# Rotary_Encoder.net
KiCad netlist of a schematic drawn in Altium Designer
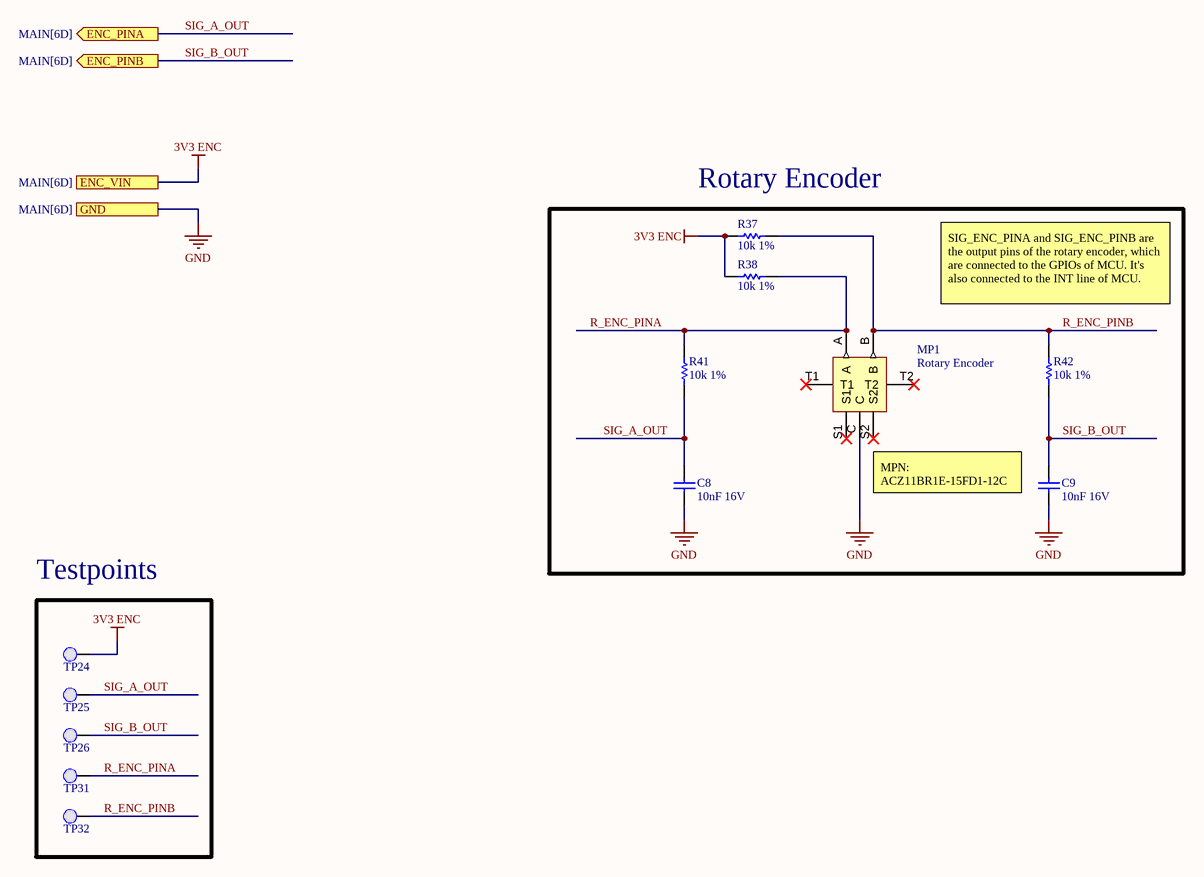
[diagram p0: Rotary Encoder.SchDoc]

(export (version "E")
  (design (tool "Eeschema 10.0.6"))
  (components
    (comp (ref "C8")
      (value "10nF 16V")
      (footprint "CAPC1608X90")
      (description "Rotary Enc-Cap Cer 0603 10NF 16V X7R 10%")
      (fields
        (field (name "MANUFACTURER") "KEMET")
        (field (name "MANUFACTURER PART NUMBER") "C0603C103K4REC7867")
      )
      (libsource (lib "Schlib1") (part "C0603C103K4REC7867"))
    )
    (comp (ref "C9")
      (value "10nF 16V")
      (footprint "CAPC1608X90")
      (description "Rotary Enc-Cap Cer 0603 10NF 16V X7R 10%")
      (fields
        (field (name "MANUFACTURER") "KEMET")
        (field (name "MANUFACTURER PART NUMBER") "C0603C103K4REC7867")
      )
      (libsource (lib "Schlib1") (part "C0603C103K4REC7867"))
    )
    (comp (ref "MP1")
      (value "Rotary Encoder")
      (footprint "Rotary Encoder")
      (description "MPN: ACZ11BR1E-15FD1-12C")
      (libsource (lib "Schlib1") (part "Rotary Encoder"))
    )
    (comp (ref "R37")
      (value "10k 1%")
      (footprint "RESC1608X55X25ML10T15")
      (description "AF0603FR-0710KL")
      (fields (field (name "MANUFACTURER") "Yageo"))
      (libsource (lib "Altium Content Vault") (part "RES"))
    )
    (comp (ref "R38")
      (value "10k 1%")
      (footprint "RESC1608X55X25ML10T15")
      (description "AF0603FR-0710KL")
      (fields (field (name "MANUFACTURER") "Yageo"))
      (libsource (lib "Altium Content Vault") (part "RES"))
    )
    (comp (ref "R41")
      (value "10k 1%")
      (footprint "RESC1608X55X25ML10T15")
      (description "AF0603FR-0710KL")
      (fields (field (name "MANUFACTURER") "Yageo"))
      (libsource (lib "Altium Content Vault") (part "RES"))
    )
    (comp (ref "R42")
      (value "10k 1%")
      (footprint "RESC1608X55X25ML10T15")
      (description "AF0603FR-0710KL")
      (fields (field (name "MANUFACTURER") "Yageo"))
      (libsource (lib "Altium Content Vault") (part "RES"))
    )
    (comp (ref "TP24")
      (value "0.1\" Pad")
      (footprint "PCBComponent")
      (libsource (lib "Components - 12.02.20 - 18.05") (part "0.1{dblquote} Pad-A.4"))
    )
    (comp (ref "TP25")
      (value "0.1\" Pad")
      (footprint "PCBComponent")
      (libsource (lib "Components - 12.02.20 - 18.05") (part "0.1{dblquote} Pad-A.4"))
    )
    (comp (ref "TP26")
      (value "0.1\" Pad")
      (footprint "PCBComponent")
      (libsource (lib "Components - 12.02.20 - 18.05") (part "0.1{dblquote} Pad-A.4"))
    )
    (comp (ref "TP31")
      (value "0.1\" Pad")
      (footprint "PCBComponent")
      (libsource (lib "Components - 12.02.20 - 18.05") (part "0.1{dblquote} Pad-A.4"))
    )
    (comp (ref "TP32")
      (value "0.1\" Pad")
      (footprint "PCBComponent")
      (libsource (lib "Components - 12.02.20 - 18.05") (part "0.1{dblquote} Pad-A.4"))
    )
  )
  (nets
    (net (code "1") (name "/R_ENC_PINA") (class "Default")
      (node (ref "MP1") (pin "A") (pinfunction "A_A") (pintype "output"))
      (node (ref "R38") (pin "1") (pinfunction "1_1") (pintype "passive"))
      (node (ref "R41") (pin "2") (pinfunction "2_2") (pintype "passive"))
      (node (ref "TP31") (pin "1") (pinfunction "PAD_1") (pintype "passive"))
    )
    (net (code "2") (name "/R_ENC_PINB") (class "Default")
      (node (ref "MP1") (pin "B") (pinfunction "B_B") (pintype "output"))
      (node (ref "R37") (pin "1") (pinfunction "1_1") (pintype "passive"))
      (node (ref "R42") (pin "2") (pinfunction "2_2") (pintype "passive"))
      (node (ref "TP32") (pin "1") (pinfunction "PAD_1") (pintype "passive"))
    )
    (net (code "3") (name "/SIG_A_OUT") (class "Default")
      (node (ref "C8") (pin "2") (pinfunction "2_2") (pintype "passive"))
      (node (ref "R41") (pin "1") (pinfunction "1_1") (pintype "passive"))
      (node (ref "TP25") (pin "1") (pinfunction "PAD_1") (pintype "passive"))
    )
    (net (code "4") (name "/SIG_B_OUT") (class "Default")
      (node (ref "C9") (pin "2") (pinfunction "2_2") (pintype "passive"))
      (node (ref "R42") (pin "1") (pinfunction "1_1") (pintype "passive"))
      (node (ref "TP26") (pin "1") (pinfunction "PAD_1") (pintype "passive"))
    )
    (net (code "5") (name "3V3 ENC") (class "Default")
      (node (ref "R37") (pin "2") (pinfunction "2_2") (pintype "passive"))
      (node (ref "R38") (pin "2") (pinfunction "2_2") (pintype "passive"))
      (node (ref "TP24") (pin "1") (pinfunction "PAD_1") (pintype "passive"))
    )
    (net (code "6") (name "GND") (class "Default")
      (node (ref "C8") (pin "1") (pinfunction "1_1") (pintype "passive"))
      (node (ref "C9") (pin "1") (pinfunction "1_1") (pintype "passive"))
      (node (ref "MP1") (pin "C") (pinfunction "C_C") (pintype "power_in"))
    )
    (net (code "7") (name "unconnected-(MP1-PadS1)") (class "Default")
      (node (ref "MP1") (pin "S1") (pinfunction "S1_S1") (pintype "passive+no_connect"))
    )
    (net (code "8") (name "unconnected-(MP1-PadS2)") (class "Default")
      (node (ref "MP1") (pin "S2") (pinfunction "S2_S2") (pintype "passive+no_connect"))
    )
    (net (code "9") (name "unconnected-(MP1-PadT1)") (class "Default")
      (node (ref "MP1") (pin "T1") (pinfunction "T1_T1") (pintype "passive+no_connect"))
    )
    (net (code "10") (name "unconnected-(MP1-PadT2)") (class "Default")
      (node (ref "MP1") (pin "T2") (pinfunction "T2_T2") (pintype "passive+no_connect"))
    )
  )
)
